# user.net
KiCad netlist of a schematic drawn in Altium Designer
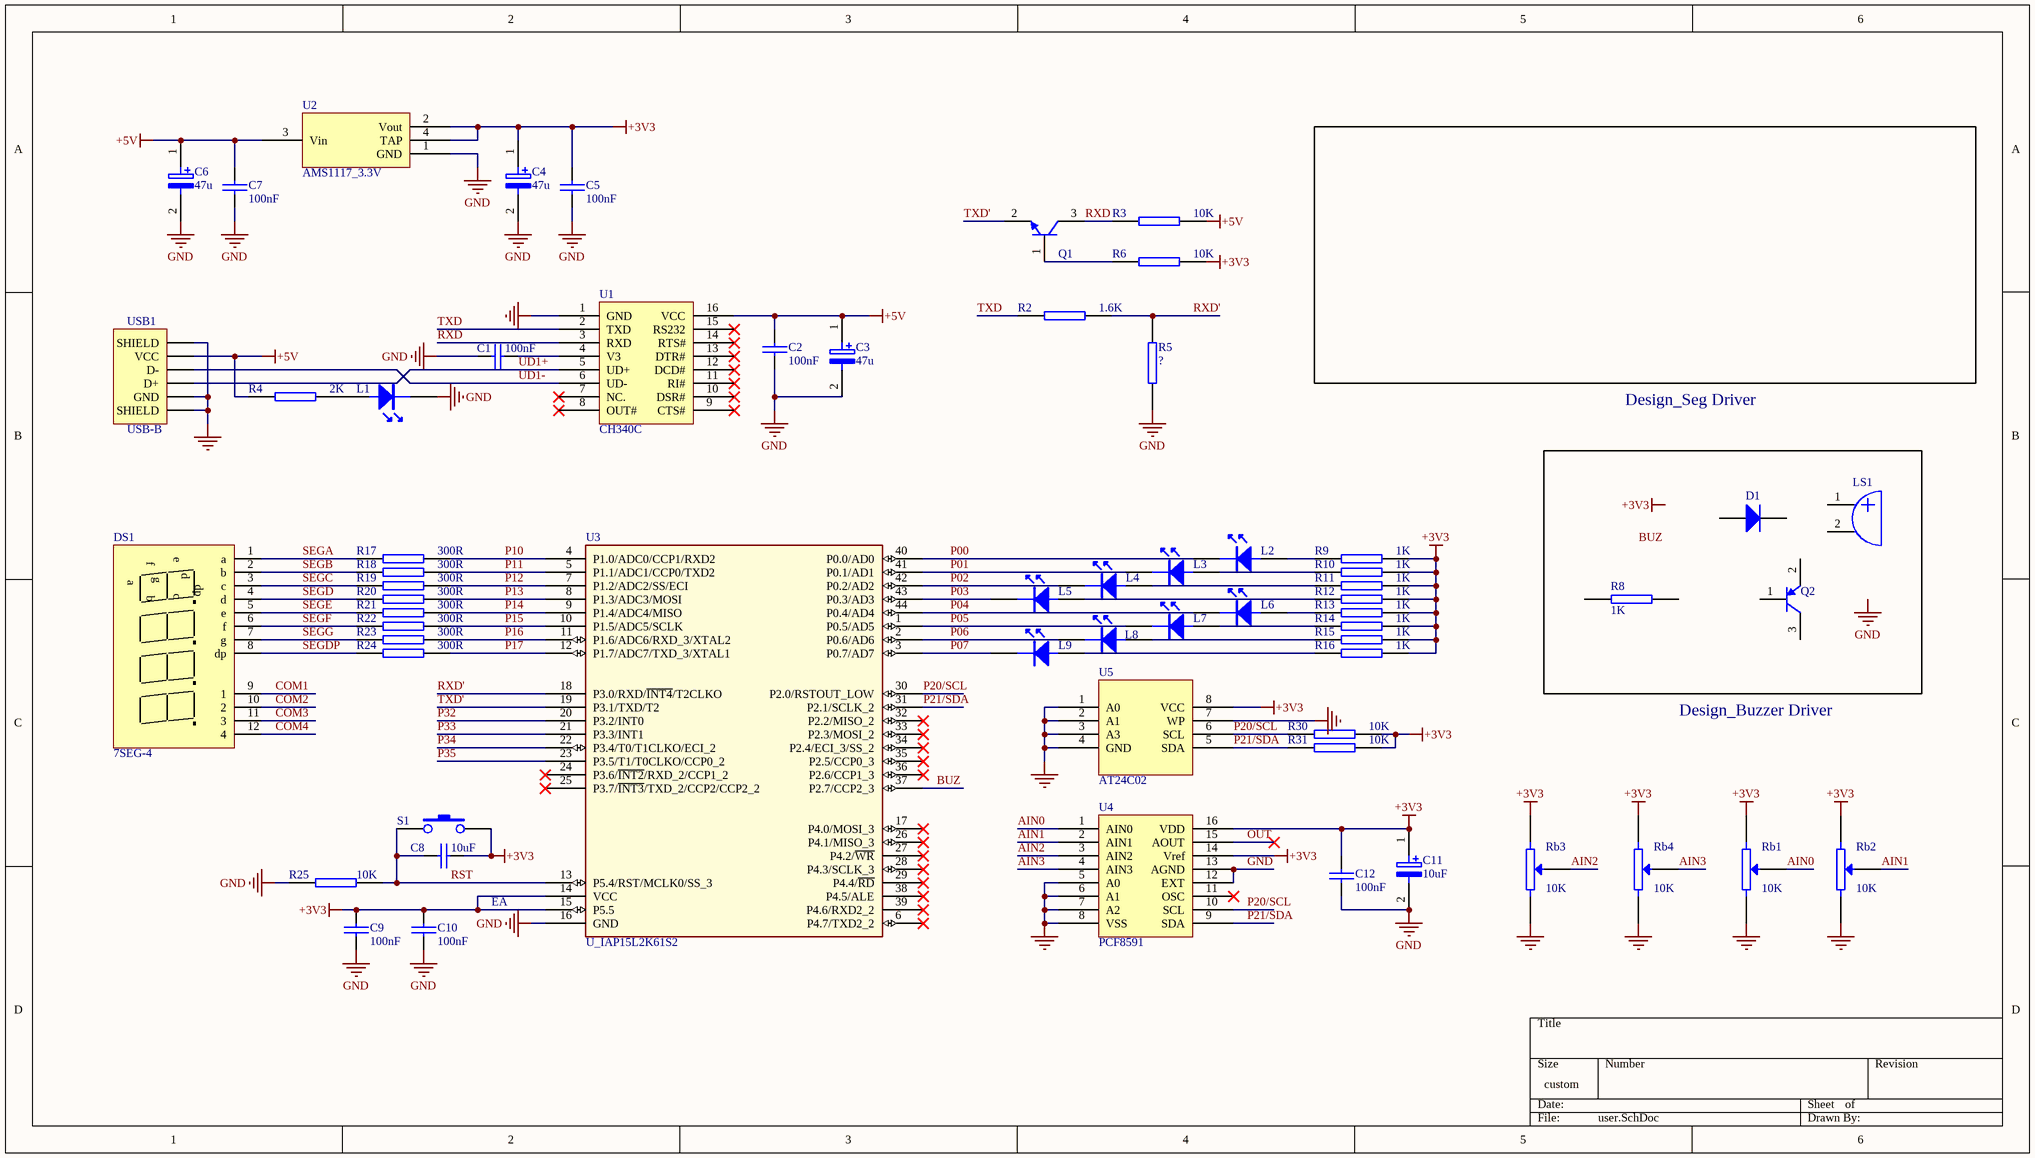
[diagram p0: user.SchDoc]

(export (version "E")
  (design (tool "Eeschema 10.0.6"))
  (components
    (comp (ref "C1") (value "100nF") (libsource (lib "") (part "CAP_1")))
    (comp (ref "C2") (value "100nF") (libsource (lib "") (part "CAP_1")))
    (comp (ref "C3")
      (value "47u")
      (description "Electrolytic Capacitor")
      (libsource (lib "user") (part "CAP-2"))
    )
    (comp (ref "C4")
      (value "47u")
      (description "Electrolytic Capacitor")
      (libsource (lib "user") (part "CAP-2"))
    )
    (comp (ref "C5")
      (value "100nF")
      (description "Capacitor")
      (libsource (lib "Altium-library") (part "C_CAP"))
    )
    (comp (ref "C6")
      (value "47u")
      (description "Electrolytic Capacitor")
      (libsource (lib "user") (part "CAP-2"))
    )
    (comp (ref "C7")
      (value "100nF")
      (description "Capacitor")
      (libsource (lib "Altium-library") (part "C_CAP"))
    )
    (comp (ref "C8") (value "10uF") (libsource (lib "") (part "CAP_1")))
    (comp (ref "C9") (value "100nF") (libsource (lib "") (part "CAP_1")))
    (comp (ref "C10") (value "100nF") (libsource (lib "") (part "CAP_1")))
    (comp (ref "C11")
      (value "10uF")
      (description "Electrolytic Capacitor")
      (libsource (lib "*") (part "ELECTRO2"))
    )
    (comp (ref "C12") (value "100nF") (description "Capacitor") (libsource (lib "*") (part "CAP")))
    (comp (ref "D1")
      (value "~")
      (description "High Conductance Fast Diode")
      (libsource (lib "Miscellaneous Devices") (part "Diode 1N914"))
    )
    (comp (ref "DS1")
      (value "7SEG-4")
      (description "4 Seven-Segment Display, Right Hand Decimal")
      (libsource (lib "*") (part "7SEG-4"))
    )
    (comp (ref "L1") (value "LED") (libsource (lib "*") (part "LED")))
    (comp (ref "L2") (value "LED") (libsource (lib "*") (part "LED")))
    (comp (ref "L3") (value "LED") (libsource (lib "*") (part "LED")))
    (comp (ref "L4") (value "LED") (libsource (lib "*") (part "LED")))
    (comp (ref "L5") (value "LED") (libsource (lib "*") (part "LED")))
    (comp (ref "L6") (value "LED") (libsource (lib "*") (part "LED")))
    (comp (ref "L7") (value "LED") (libsource (lib "*") (part "LED")))
    (comp (ref "L8") (value "LED") (libsource (lib "*") (part "LED")))
    (comp (ref "L9") (value "LED") (libsource (lib "*") (part "LED")))
    (comp (ref "LS1") (value "S_BUZZER") (libsource (lib "Altium") (part "S_BUZZER")))
    (comp (ref "Q1") (value "8050-SOT23") (description "PNP-S8050") (libsource (lib "Altium") (part "Q_NPN")))
    (comp (ref "Q2")
      (value "~")
      (description "PNP General Purpose Amplifier")
      (libsource (lib "Miscellaneous Devices") (part "2N3906"))
    )
    (comp (ref "R2") (value "1.6K") (libsource (lib "*") (part "RES2")))
    (comp (ref "R3") (value "10K") (libsource (lib "*") (part "RES2")))
    (comp (ref "R4") (value "2K") (libsource (lib "*") (part "RES2")))
    (comp (ref "R5") (value "?") (libsource (lib "*") (part "RES2")))
    (comp (ref "R6") (value "10K") (libsource (lib "*") (part "RES2")))
    (comp (ref "R8") (value "1K") (libsource (lib "*") (part "RES2")))
    (comp (ref "R9") (value "1K") (libsource (lib "*") (part "RES2")))
    (comp (ref "R10") (value "1K") (libsource (lib "*") (part "RES2")))
    (comp (ref "R11") (value "1K") (libsource (lib "*") (part "RES2")))
    (comp (ref "R12") (value "1K") (libsource (lib "*") (part "RES2")))
    (comp (ref "R13") (value "1K") (libsource (lib "*") (part "RES2")))
    (comp (ref "R14") (value "1K") (libsource (lib "*") (part "RES2")))
    (comp (ref "R15") (value "1K") (libsource (lib "*") (part "RES2")))
    (comp (ref "R16") (value "1K") (libsource (lib "*") (part "RES2")))
    (comp (ref "R17") (value "300R") (libsource (lib "*") (part "RES2")))
    (comp (ref "R18") (value "300R") (libsource (lib "*") (part "RES2")))
    (comp (ref "R19") (value "300R") (libsource (lib "*") (part "RES2")))
    (comp (ref "R20") (value "300R") (libsource (lib "*") (part "RES2")))
    (comp (ref "R21") (value "300R") (libsource (lib "*") (part "RES2")))
    (comp (ref "R22") (value "300R") (libsource (lib "*") (part "RES2")))
    (comp (ref "R23") (value "300R") (libsource (lib "*") (part "RES2")))
    (comp (ref "R24") (value "300R") (libsource (lib "*") (part "RES2")))
    (comp (ref "R25") (value "10K") (libsource (lib "*") (part "RES2")))
    (comp (ref "R30") (value "10K") (libsource (lib "*") (part "RES2")))
    (comp (ref "R31") (value "10K") (libsource (lib "*") (part "RES2")))
    (comp (ref "Rb1") (value "10K") (description "Potentiometer") (libsource (lib "*") (part "POT2")))
    (comp (ref "Rb2") (value "10K") (description "Potentiometer") (libsource (lib "*") (part "POT2")))
    (comp (ref "Rb3") (value "10K") (description "Potentiometer") (libsource (lib "*") (part "POT2")))
    (comp (ref "Rb4") (value "10K") (description "Potentiometer") (libsource (lib "*") (part "POT2")))
    (comp (ref "S1") (value "SW-PB") (libsource (lib "user") (part "SW-PB")))
    (comp (ref "U1") (value "CH340C") (libsource (lib "user") (part "CH340C")))
    (comp (ref "U2")
      (value "AMS1117_3.3V")
      (description "POWER")
      (libsource (lib "Altium-library") (part "U_ASM1117"))
    )
    (comp (ref "U3")
      (value "U_IAP15L2K61S2")
      (description "MCU")
      (libsource (lib "Company-library_2018年11月21日") (part "U_IAP15F2K61S2"))
    )
    (comp (ref "U4") (value "PCF8591") (libsource (lib "*") (part "PCF8591")))
    (comp (ref "U5") (value "AT24C02") (libsource (lib "*") (part "AT24C02")))
    (comp (ref "USB1") (value "USB-B") (description "Connector") (libsource (lib "*") (part "USB_A")))
  )
  (nets
    (net (code "1") (name "+3V3") (class "Default")
      (node (ref "C10") (pin "1") (pintype "passive"))
      (node (ref "C11") (pin "1") (pinfunction "1_1") (pintype "passive"))
      (node (ref "C12") (pin "2") (pinfunction "2_2") (pintype "passive"))
      (node (ref "C4") (pin "1") (pinfunction "1_1") (pintype "passive"))
      (node (ref "C5") (pin "2") (pinfunction "2_2") (pintype "passive"))
      (node (ref "C8") (pin "2") (pintype "passive"))
      (node (ref "C9") (pin "1") (pintype "passive"))
      (node (ref "R10") (pin "2") (pinfunction "2_2") (pintype "passive"))
      (node (ref "R11") (pin "2") (pinfunction "2_2") (pintype "passive"))
      (node (ref "R12") (pin "2") (pinfunction "2_2") (pintype "passive"))
      (node (ref "R13") (pin "2") (pinfunction "2_2") (pintype "passive"))
      (node (ref "R14") (pin "2") (pinfunction "2_2") (pintype "passive"))
      (node (ref "R15") (pin "2") (pinfunction "2_2") (pintype "passive"))
      (node (ref "R16") (pin "2") (pinfunction "2_2") (pintype "passive"))
      (node (ref "R30") (pin "1") (pinfunction "1_1") (pintype "passive"))
      (node (ref "R31") (pin "1") (pinfunction "1_1") (pintype "passive"))
      (node (ref "R6") (pin "1") (pinfunction "1_1") (pintype "passive"))
      (node (ref "R9") (pin "2") (pinfunction "2_2") (pintype "passive"))
      (node (ref "Rb1") (pin "1") (pinfunction "1_1") (pintype "passive"))
      (node (ref "Rb2") (pin "1") (pinfunction "1_1") (pintype "passive"))
      (node (ref "Rb3") (pin "1") (pinfunction "1_1") (pintype "passive"))
      (node (ref "Rb4") (pin "1") (pinfunction "1_1") (pintype "passive"))
      (node (ref "S1") (pin "2") (pinfunction "2_2") (pintype "passive"))
      (node (ref "U2") (pin "2") (pinfunction "Vout_2") (pintype "passive"))
      (node (ref "U2") (pin "4") (pinfunction "TAP_4") (pintype "passive"))
      (node (ref "U3") (pin "14") (pinfunction "VCC_14") (pintype "power_in"))
      (node (ref "U3") (pin "15") (pinfunction "P5.5_15") (pintype "bidirectional"))
      (node (ref "U4") (pin "14") (pinfunction "Vref_14") (pintype "passive"))
      (node (ref "U4") (pin "16") (pinfunction "VDD_16") (pintype "passive"))
      (node (ref "U5") (pin "8") (pinfunction "VCC_8") (pintype "passive"))
    )
    (net (code "2") (name "+5V") (class "Default")
      (node (ref "C2") (pin "1") (pintype "passive"))
      (node (ref "C3") (pin "1") (pinfunction "1_1") (pintype "passive"))
      (node (ref "C6") (pin "1") (pinfunction "1_1") (pintype "passive"))
      (node (ref "C7") (pin "2") (pinfunction "2_2") (pintype "passive"))
      (node (ref "R3") (pin "1") (pinfunction "1_1") (pintype "passive"))
      (node (ref "R4") (pin "2") (pinfunction "2_2") (pintype "passive"))
      (node (ref "U1") (pin "16") (pinfunction "VCC_16") (pintype "passive"))
      (node (ref "U2") (pin "3") (pinfunction "Vin_3") (pintype "passive"))
      (node (ref "USB1") (pin "1") (pinfunction "VCC_1") (pintype "passive"))
    )
    (net (code "3") (name "/AIN0") (class "Default")
      (node (ref "Rb1") (pin "2") (pinfunction "W_2") (pintype "passive"))
      (node (ref "U4") (pin "1") (pinfunction "AIN0_1") (pintype "passive"))
    )
    (net (code "4") (name "/AIN1") (class "Default")
      (node (ref "Rb2") (pin "2") (pinfunction "W_2") (pintype "passive"))
      (node (ref "U4") (pin "2") (pinfunction "AIN1_2") (pintype "passive"))
    )
    (net (code "5") (name "/AIN2") (class "Default")
      (node (ref "Rb3") (pin "2") (pinfunction "W_2") (pintype "passive"))
      (node (ref "U4") (pin "3") (pinfunction "AIN2_3") (pintype "passive"))
    )
    (net (code "6") (name "/AIN3") (class "Default")
      (node (ref "Rb4") (pin "2") (pinfunction "W_2") (pintype "passive"))
      (node (ref "U4") (pin "4") (pinfunction "AIN3_4") (pintype "passive"))
    )
    (net (code "7") (name "/BUZ") (class "Default")
      (node (ref "U3") (pin "37") (pinfunction "P2.7/CCP2_3_37") (pintype "bidirectional"))
    )
    (net (code "8") (name "/COM1") (class "Default")
      (node (ref "DS1") (pin "9") (pinfunction "1_9") (pintype "passive"))
    )
    (net (code "9") (name "/COM2") (class "Default")
      (node (ref "DS1") (pin "10") (pinfunction "2_10") (pintype "passive"))
    )
    (net (code "10") (name "/COM3") (class "Default")
      (node (ref "DS1") (pin "11") (pinfunction "3_11") (pintype "passive"))
    )
    (net (code "11") (name "/COM4") (class "Default")
      (node (ref "DS1") (pin "12") (pinfunction "4_12") (pintype "passive"))
    )
    (net (code "12") (name "/OUT") (class "Default")
      (node (ref "U4") (pin "15") (pinfunction "AOUT_15") (pintype "passive+no_connect"))
    )
    (net (code "13") (name "/P00") (class "Default")
      (node (ref "L2") (pin "2") (pinfunction "K_2") (pintype "passive"))
      (node (ref "U3") (pin "40") (pinfunction "P0.0/AD0_40") (pintype "bidirectional"))
    )
    (net (code "14") (name "/P01") (class "Default")
      (node (ref "L3") (pin "2") (pinfunction "K_2") (pintype "passive"))
      (node (ref "U3") (pin "41") (pinfunction "P0.1/AD1_41") (pintype "bidirectional"))
    )
    (net (code "15") (name "/P02") (class "Default")
      (node (ref "L4") (pin "2") (pinfunction "K_2") (pintype "passive"))
      (node (ref "U3") (pin "42") (pinfunction "P0.2/AD2_42") (pintype "bidirectional"))
    )
    (net (code "16") (name "/P03") (class "Default")
      (node (ref "L5") (pin "2") (pinfunction "K_2") (pintype "passive"))
      (node (ref "U3") (pin "43") (pinfunction "P0.3/AD3_43") (pintype "bidirectional"))
    )
    (net (code "17") (name "/P04") (class "Default")
      (node (ref "L6") (pin "2") (pinfunction "K_2") (pintype "passive"))
      (node (ref "U3") (pin "44") (pinfunction "P0.4/AD4_44") (pintype "bidirectional"))
    )
    (net (code "18") (name "/P05") (class "Default")
      (node (ref "L7") (pin "2") (pinfunction "K_2") (pintype "passive"))
      (node (ref "U3") (pin "1") (pinfunction "P0.5/AD5_1") (pintype "bidirectional"))
    )
    (net (code "19") (name "/P06") (class "Default")
      (node (ref "L8") (pin "2") (pinfunction "K_2") (pintype "passive"))
      (node (ref "U3") (pin "2") (pinfunction "P0.6/AD6_2") (pintype "bidirectional"))
    )
    (net (code "20") (name "/P07") (class "Default")
      (node (ref "L9") (pin "2") (pinfunction "K_2") (pintype "passive"))
      (node (ref "U3") (pin "3") (pinfunction "P0.7/AD7_3") (pintype "bidirectional"))
    )
    (net (code "21") (name "/P10") (class "Default")
      (node (ref "R17") (pin "2") (pinfunction "2_2") (pintype "passive"))
      (node (ref "U3") (pin "4") (pinfunction "P1.0/ADC0/CCP1/RXD2_4") (pintype "passive"))
    )
    (net (code "22") (name "/P11") (class "Default")
      (node (ref "R18") (pin "2") (pinfunction "2_2") (pintype "passive"))
      (node (ref "U3") (pin "5") (pinfunction "P1.1/ADC1/CCP0/TXD2_5") (pintype "passive"))
    )
    (net (code "23") (name "/P12") (class "Default")
      (node (ref "R19") (pin "2") (pinfunction "2_2") (pintype "passive"))
      (node (ref "U3") (pin "7") (pinfunction "P1.2/ADC2/SS/ECI_7") (pintype "passive"))
    )
    (net (code "24") (name "/P13") (class "Default")
      (node (ref "R20") (pin "2") (pinfunction "2_2") (pintype "passive"))
      (node (ref "U3") (pin "8") (pinfunction "P1.3/ADC3/MOSI_8") (pintype "passive"))
    )
    (net (code "25") (name "/P14") (class "Default")
      (node (ref "R21") (pin "2") (pinfunction "2_2") (pintype "passive"))
      (node (ref "U3") (pin "9") (pinfunction "P1.4/ADC4/MISO_9") (pintype "passive"))
    )
    (net (code "26") (name "/P15") (class "Default")
      (node (ref "R22") (pin "2") (pinfunction "2_2") (pintype "passive"))
      (node (ref "U3") (pin "10") (pinfunction "P1.5/ADC5/SCLK_10") (pintype "passive"))
    )
    (net (code "27") (name "/P16") (class "Default")
      (node (ref "R23") (pin "2") (pinfunction "2_2") (pintype "passive"))
      (node (ref "U3") (pin "11") (pinfunction "P1.6/ADC6/RXD_3/XTAL2_11") (pintype "bidirectional"))
    )
    (net (code "28") (name "/P17") (class "Default")
      (node (ref "R24") (pin "2") (pinfunction "2_2") (pintype "passive"))
      (node (ref "U3") (pin "12") (pinfunction "P1.7/ADC7/TXD_3/XTAL1_12") (pintype "bidirectional"))
    )
    (net (code "29") (name "/P20{slash}SCL") (class "Default")
      (node (ref "R30") (pin "2") (pinfunction "2_2") (pintype "passive"))
      (node (ref "U3") (pin "30") (pinfunction "P2.0/RSTOUT_LOW_30") (pintype "bidirectional"))
      (node (ref "U4") (pin "10") (pinfunction "SCL_10") (pintype "passive"))
      (node (ref "U5") (pin "6") (pinfunction "SCL_6") (pintype "passive"))
    )
    (net (code "30") (name "/P21{slash}SDA") (class "Default")
      (node (ref "R31") (pin "2") (pinfunction "2_2") (pintype "passive"))
      (node (ref "U3") (pin "31") (pinfunction "P2.1/SCLK_2_31") (pintype "bidirectional"))
      (node (ref "U4") (pin "9") (pinfunction "SDA_9") (pintype "passive"))
      (node (ref "U5") (pin "5") (pinfunction "SDA_5") (pintype "passive"))
    )
    (net (code "31") (name "/P32") (class "Default")
      (node (ref "U3") (pin "20") (pinfunction "P3.2/INT0_20") (pintype "passive"))
    )
    (net (code "32") (name "/P33") (class "Default")
      (node (ref "U3") (pin "21") (pinfunction "P3.3/INT1_21") (pintype "passive"))
    )
    (net (code "33") (name "/P34") (class "Default")
      (node (ref "U3") (pin "22") (pinfunction "P3.4/T0/T1CLKO/ECI_2_22") (pintype "bidirectional"))
    )
    (net (code "34") (name "/P35") (class "Default")
      (node (ref "U3") (pin "23") (pinfunction "P3.5/T1/T0CLKO/CCP0_2_23") (pintype "passive"))
    )
    (net (code "35") (name "/RST") (class "Default")
      (node (ref "C8") (pin "1") (pintype "passive"))
      (node (ref "R25") (pin "1") (pinfunction "1_1") (pintype "passive"))
      (node (ref "S1") (pin "1") (pinfunction "1_1") (pintype "passive"))
      (node (ref "U3") (pin "13") (pinfunction "P5.4/RST/MCLK0/SS_3_13") (pintype "bidirectional"))
    )
    (net (code "36") (name "/RXD") (class "Default")
      (node (ref "Q1") (pin "3") (pinfunction "C_3") (pintype "passive"))
      (node (ref "R3") (pin "2") (pinfunction "2_2") (pintype "passive"))
      (node (ref "U1") (pin "3") (pinfunction "RXD_3") (pintype "passive"))
    )
    (net (code "37") (name "/RXD'") (class "Default")
      (node (ref "R2") (pin "1") (pinfunction "1_1") (pintype "passive"))
      (node (ref "R5") (pin "1") (pinfunction "1_1") (pintype "passive"))
      (node (ref "U3") (pin "18") (pinfunction "P3.0/RXD/~{INT4}/T2CLKO_18") (pintype "passive"))
    )
    (net (code "38") (name "/SEGA") (class "Default")
      (node (ref "DS1") (pin "1") (pinfunction "a_1") (pintype "passive"))
      (node (ref "R17") (pin "1") (pinfunction "1_1") (pintype "passive"))
    )
    (net (code "39") (name "/SEGB") (class "Default")
      (node (ref "DS1") (pin "2") (pinfunction "b_2") (pintype "passive"))
      (node (ref "R18") (pin "1") (pinfunction "1_1") (pintype "passive"))
    )
    (net (code "40") (name "/SEGC") (class "Default")
      (node (ref "DS1") (pin "3") (pinfunction "c_3") (pintype "passive"))
      (node (ref "R19") (pin "1") (pinfunction "1_1") (pintype "passive"))
    )
    (net (code "41") (name "/SEGD") (class "Default")
      (node (ref "DS1") (pin "4") (pinfunction "d_4") (pintype "passive"))
      (node (ref "R20") (pin "1") (pinfunction "1_1") (pintype "passive"))
    )
    (net (code "42") (name "/SEGDP") (class "Default")
      (node (ref "DS1") (pin "8") (pinfunction "dp_8") (pintype "passive"))
      (node (ref "R24") (pin "1") (pinfunction "1_1") (pintype "passive"))
    )
    (net (code "43") (name "/SEGE") (class "Default")
      (node (ref "DS1") (pin "5") (pinfunction "e_5") (pintype "passive"))
      (node (ref "R21") (pin "1") (pinfunction "1_1") (pintype "passive"))
    )
    (net (code "44") (name "/SEGF") (class "Default")
      (node (ref "DS1") (pin "6") (pinfunction "f_6") (pintype "passive"))
      (node (ref "R22") (pin "1") (pinfunction "1_1") (pintype "passive"))
    )
    (net (code "45") (name "/SEGG") (class "Default")
      (node (ref "DS1") (pin "7") (pinfunction "g_7") (pintype "passive"))
      (node (ref "R23") (pin "1") (pinfunction "1_1") (pintype "passive"))
    )
    (net (code "46") (name "/TXD") (class "Default")
      (node (ref "R2") (pin "2") (pinfunction "2_2") (pintype "passive"))
      (node (ref "U1") (pin "2") (pinfunction "TXD_2") (pintype "passive"))
    )
    (net (code "47") (name "/TXD'") (class "Default")
      (node (ref "Q1") (pin "2") (pinfunction "E_2") (pintype "passive"))
      (node (ref "U3") (pin "19") (pinfunction "P3.1/TXD/T2_19") (pintype "passive"))
    )
    (net (code "48") (name "/UD1+") (class "Default")
      (node (ref "U1") (pin "5") (pinfunction "UD+_5") (pintype "passive"))
      (node (ref "USB1") (pin "3") (pinfunction "D+_3") (pintype "passive"))
    )
    (net (code "49") (name "/UD1-") (class "Default")
      (node (ref "U1") (pin "6") (pinfunction "UD-_6") (pintype "passive"))
      (node (ref "USB1") (pin "2") (pinfunction "D-_2") (pintype "passive"))
    )
    (net (code "50") (name "GND") (class "Default")
      (node (ref "C1") (pin "1") (pintype "passive"))
      (node (ref "C10") (pin "2") (pintype "passive"))
      (node (ref "C11") (pin "2") (pinfunction "2_2") (pintype "passive"))
      (node (ref "C12") (pin "1") (pinfunction "1_1") (pintype "passive"))
      (node (ref "C2") (pin "2") (pintype "passive"))
      (node (ref "C3") (pin "2") (pinfunction "2_2") (pintype "passive"))
      (node (ref "C4") (pin "2") (pinfunction "2_2") (pintype "passive"))
      (node (ref "C5") (pin "1") (pinfunction "1_1") (pintype "passive"))
      (node (ref "C6") (pin "2") (pinfunction "2_2") (pintype "passive"))
      (node (ref "C7") (pin "1") (pinfunction "1_1") (pintype "passive"))
      (node (ref "C9") (pin "2") (pintype "passive"))
      (node (ref "L1") (pin "2") (pinfunction "K_2") (pintype "passive"))
      (node (ref "R25") (pin "2") (pinfunction "2_2") (pintype "passive"))
      (node (ref "R5") (pin "2") (pinfunction "2_2") (pintype "passive"))
      (node (ref "Rb1") (pin "3") (pinfunction "2_3") (pintype "passive"))
      (node (ref "Rb2") (pin "3") (pinfunction "2_3") (pintype "passive"))
      (node (ref "Rb3") (pin "3") (pinfunction "2_3") (pintype "passive"))
      (node (ref "Rb4") (pin "3") (pinfunction "2_3") (pintype "passive"))
      (node (ref "U1") (pin "1") (pinfunction "GND_1") (pintype "passive"))
      (node (ref "U2") (pin "1") (pinfunction "GND_1") (pintype "passive"))
      (node (ref "U3") (pin "16") (pinfunction "GND_16") (pintype "power_in"))
      (node (ref "U4") (pin "12") (pinfunction "EXT_12") (pintype "passive"))
      (node (ref "U4") (pin "13") (pinfunction "AGND_13") (pintype "passive"))
      (node (ref "U4") (pin "5") (pinfunction "A0_5") (pintype "passive"))
      (node (ref "U4") (pin "6") (pinfunction "A1_6") (pintype "passive"))
      (node (ref "U4") (pin "7") (pinfunction "A2_7") (pintype "passive"))
      (node (ref "U4") (pin "8") (pinfunction "VSS_8") (pintype "passive"))
      (node (ref "U5") (pin "1") (pinfunction "A0_1") (pintype "passive"))
      (node (ref "U5") (pin "2") (pinfunction "A1_2") (pintype "passive"))
      (node (ref "U5") (pin "3") (pinfunction "A3_3") (pintype "passive"))
      (node (ref "U5") (pin "4") (pinfunction "GND_4") (pintype "passive"))
      (node (ref "U5") (pin "7") (pinfunction "WP_7") (pintype "passive"))
      (node (ref "USB1") (pin "4") (pinfunction "GND_4") (pintype "passive"))
      (node (ref "USB1") (pin "5") (pinfunction "SHIELD_5") (pintype "passive"))
      (node (ref "USB1") (pin "6") (pinfunction "SHIELD_6") (pintype "passive"))
    )
    (net (code "51") (name "Net-(L1-A)") (class "Default")
      (node (ref "L1") (pin "1") (pinfunction "A_1") (pintype "passive"))
      (node (ref "R4") (pin "1") (pinfunction "1_1") (pintype "passive"))
    )
    (net (code "52") (name "Net-(L2-A)") (class "Default")
      (node (ref "L2") (pin "1") (pinfunction "A_1") (pintype "passive"))
      (node (ref "R9") (pin "1") (pinfunction "1_1") (pintype "passive"))
    )
    (net (code "53") (name "Net-(L3-A)") (class "Default")
      (node (ref "L3") (pin "1") (pinfunction "A_1") (pintype "passive"))
      (node (ref "R10") (pin "1") (pinfunction "1_1") (pintype "passive"))
    )
    (net (code "54") (name "Net-(L4-A)") (class "Default")
      (node (ref "L4") (pin "1") (pinfunction "A_1") (pintype "passive"))
      (node (ref "R11") (pin "1") (pinfunction "1_1") (pintype "passive"))
    )
    (net (code "55") (name "Net-(L5-A)") (class "Default")
      (node (ref "L5") (pin "1") (pinfunction "A_1") (pintype "passive"))
      (node (ref "R12") (pin "1") (pinfunction "1_1") (pintype "passive"))
    )
    (net (code "56") (name "Net-(L6-A)") (class "Default")
      (node (ref "L6") (pin "1") (pinfunction "A_1") (pintype "passive"))
      (node (ref "R13") (pin "1") (pinfunction "1_1") (pintype "passive"))
    )
    (net (code "57") (name "Net-(L7-A)") (class "Default")
      (node (ref "L7") (pin "1") (pinfunction "A_1") (pintype "passive"))
      (node (ref "R14") (pin "1") (pinfunction "1_1") (pintype "passive"))
    )
    (net (code "58") (name "Net-(L8-A)") (class "Default")
      (node (ref "L8") (pin "1") (pinfunction "A_1") (pintype "passive"))
      (node (ref "R15") (pin "1") (pinfunction "1_1") (pintype "passive"))
    )
    (net (code "59") (name "Net-(L9-A)") (class "Default")
      (node (ref "L9") (pin "1") (pinfunction "A_1") (pintype "passive"))
      (node (ref "R16") (pin "1") (pinfunction "1_1") (pintype "passive"))
    )
    (net (code "60") (name "Net-(Q1-B)") (class "Default")
      (node (ref "Q1") (pin "1") (pinfunction "B_1") (pintype "passive"))
      (node (ref "R6") (pin "2") (pinfunction "2_2") (pintype "passive"))
    )
    (net (code "61") (name "Net-(U1-V3)") (class "Default")
      (node (ref "C1") (pin "2") (pintype "passive"))
      (node (ref "U1") (pin "4") (pinfunction "V3_4") (pintype "passive"))
    )
    (net (code "62") (name "unconnected-(D1-A-Pad1)") (class "Default")
      (node (ref "D1") (pin "1") (pinfunction "A_1") (pintype "passive"))
    )
    (net (code "63") (name "unconnected-(D1-K-Pad2)") (class "Default")
      (node (ref "D1") (pin "2") (pinfunction "K_2") (pintype "passive"))
    )
    (net (code "64") (name "unconnected-(LS1-Pad1)") (class "Default")
      (node (ref "LS1") (pin "1") (pinfunction "1_1") (pintype "passive"))
    )
    (net (code "65") (name "unconnected-(LS1-Pad2)") (class "Default")
      (node (ref "LS1") (pin "2") (pinfunction "2_2") (pintype "passive"))
    )
    (net (code "66") (name "unconnected-(Q2-B-Pad1)") (class "Default")
      (node (ref "Q2") (pin "1") (pinfunction "B_1") (pintype "passive"))
    )
    (net (code "67") (name "unconnected-(Q2-C-Pad3)") (class "Default")
      (node (ref "Q2") (pin "3") (pinfunction "C_3") (pintype "passive"))
    )
    (net (code "68") (name "unconnected-(Q2-E-Pad2)") (class "Default")
      (node (ref "Q2") (pin "2") (pinfunction "E_2") (pintype "passive"))
    )
    (net (code "69") (name "unconnected-(R8-Pad1)") (class "Default")
      (node (ref "R8") (pin "1") (pinfunction "1_1") (pintype "passive"))
    )
    (net (code "70") (name "unconnected-(R8-Pad2)") (class "Default")
      (node (ref "R8") (pin "2") (pinfunction "2_2") (pintype "passive"))
    )
    (net (code "71") (name "unconnected-(U1-CTS#-Pad9)") (class "Default")
      (node (ref "U1") (pin "9") (pinfunction "CTS#_9") (pintype "passive+no_connect"))
    )
    (net (code "72") (name "unconnected-(U1-DCD#-Pad12)") (class "Default")
      (node (ref "U1") (pin "12") (pinfunction "DCD#_12") (pintype "passive+no_connect"))
    )
    (net (code "73") (name "unconnected-(U1-DSR#-Pad10)") (class "Default")
      (node (ref "U1") (pin "10") (pinfunction "DSR#_10") (pintype "passive+no_connect"))
    )
    (net (code "74") (name "unconnected-(U1-DTR#-Pad13)") (class "Default")
      (node (ref "U1") (pin "13") (pinfunction "DTR#_13") (pintype "passive+no_connect"))
    )
    (net (code "75") (name "unconnected-(U1-NC.-Pad7)") (class "Default")
      (node (ref "U1") (pin "7") (pinfunction "NC._7") (pintype "passive+no_connect"))
    )
    (net (code "76") (name "unconnected-(U1-OUT#-Pad8)") (class "Default")
      (node (ref "U1") (pin "8") (pinfunction "OUT#_8") (pintype "passive+no_connect"))
    )
    (net (code "77") (name "unconnected-(U1-RI#-Pad11)") (class "Default")
      (node (ref "U1") (pin "11") (pinfunction "RI#_11") (pintype "passive+no_connect"))
    )
    (net (code "78") (name "unconnected-(U1-RS232-Pad15)") (class "Default")
      (node (ref "U1") (pin "15") (pinfunction "RS232_15") (pintype "passive+no_connect"))
    )
    (net (code "79") (name "unconnected-(U1-RTS#-Pad14)") (class "Default")
      (node (ref "U1") (pin "14") (pinfunction "RTS#_14") (pintype "passive+no_connect"))
    )
    (net (code "80") (name "unconnected-(U3-P2.2{slash}MISO_2-Pad32)") (class "Default")
      (node (ref "U3") (pin "32") (pinfunction "P2.2/MISO_2_32") (pintype "bidirectional+no_connect"))
    )
    (net (code "81") (name "unconnected-(U3-P2.3{slash}MOSI_2-Pad33)") (class "Default")
      (node (ref "U3") (pin "33") (pinfunction "P2.3/MOSI_2_33") (pintype "bidirectional+no_connect"))
    )
    (net (code "82") (name "unconnected-(U3-P2.4{slash}ECI_3{slash}SS_2-Pad34)") (class "Default")
      (node (ref "U3") (pin "34") (pinfunction "P2.4/ECI_3/SS_2_34") (pintype "bidirectional+no_connect"))
    )
    (net (code "83") (name "unconnected-(U3-P2.5{slash}CCP0_3-Pad35)") (class "Default")
      (node (ref "U3") (pin "35") (pinfunction "P2.5/CCP0_3_35") (pintype "bidirectional+no_connect"))
    )
    (net (code "84") (name "unconnected-(U3-P2.6{slash}CCP1_3-Pad36)") (class "Default")
      (node (ref "U3") (pin "36") (pinfunction "P2.6/CCP1_3_36") (pintype "bidirectional+no_connect"))
    )
    (net (code "85") (name "unconnected-(U3-P3.6{slash}~{INT2}{slash}RXD_2{slash}CCP1_2-Pad24)") (class "Default")
      (node (ref "U3") (pin "24") (pinfunction "P3.6/~{INT2}/RXD_2/CCP1_2_24") (pintype "passive+no_connect"))
    )
    (net (code "86") (name "unconnected-(U3-P3.7{slash}~{INT3}{slash}TXD_2{slash}CCP2{slash}CCP2_2-Pad25)") (class "Default")
      (node (ref "U3") (pin "25") (pinfunction "P3.7/~{INT3}/TXD_2/CCP2/CCP2_2_25") (pintype "passive+no_connect"))
    )
    (net (code "87") (name "unconnected-(U3-P4.0{slash}MOSI_3-Pad17)") (class "Default")
      (node (ref "U3") (pin "17") (pinfunction "P4.0/MOSI_3_17") (pintype "bidirectional+no_connect"))
    )
    (net (code "88") (name "unconnected-(U3-P4.1{slash}MISO_3-Pad26)") (class "Default")
      (node (ref "U3") (pin "26") (pinfunction "P4.1/MISO_3_26") (pintype "bidirectional+no_connect"))
    )
    (net (code "89") (name "unconnected-(U3-P4.2{slash}~{WR}-Pad27)") (class "Default")
      (node (ref "U3") (pin "27") (pinfunction "P4.2/~{WR}_27") (pintype "passive+no_connect"))
    )
    (net (code "90") (name "unconnected-(U3-P4.3{slash}SCLK_3-Pad28)") (class "Default")
      (node (ref "U3") (pin "28") (pinfunction "P4.3/SCLK_3_28") (pintype "bidirectional+no_connect"))
    )
    (net (code "91") (name "unconnected-(U3-P4.4{slash}~{RD}-Pad29)") (class "Default")
      (node (ref "U3") (pin "29") (pinfunction "P4.4/~{RD}_29") (pintype "passive+no_connect"))
    )
    (net (code "92") (name "unconnected-(U3-P4.5{slash}ALE-Pad38)") (class "Default")
      (node (ref "U3") (pin "38") (pinfunction "P4.5/ALE_38") (pintype "passive+no_connect"))
    )
    (net (code "93") (name "unconnected-(U3-P4.6{slash}RXD2_2-Pad39)") (class "Default")
      (node (ref "U3") (pin "39") (pinfunction "P4.6/RXD2_2_39") (pintype "passive+no_connect"))
    )
    (net (code "94") (name "unconnected-(U3-P4.7{slash}TXD2_2-Pad6)") (class "Default")
      (node (ref "U3") (pin "6") (pinfunction "P4.7/TXD2_2_6") (pintype "bidirectional+no_connect"))
    )
    (net (code "95") (name "unconnected-(U4-OSC-Pad11)") (class "Default")
      (node (ref "U4") (pin "11") (pinfunction "OSC_11") (pintype "passive+no_connect"))
    )
  )
)
